# TOP_SENSOR_V2.net
KiCad netlist of a schematic drawn in EAGLE
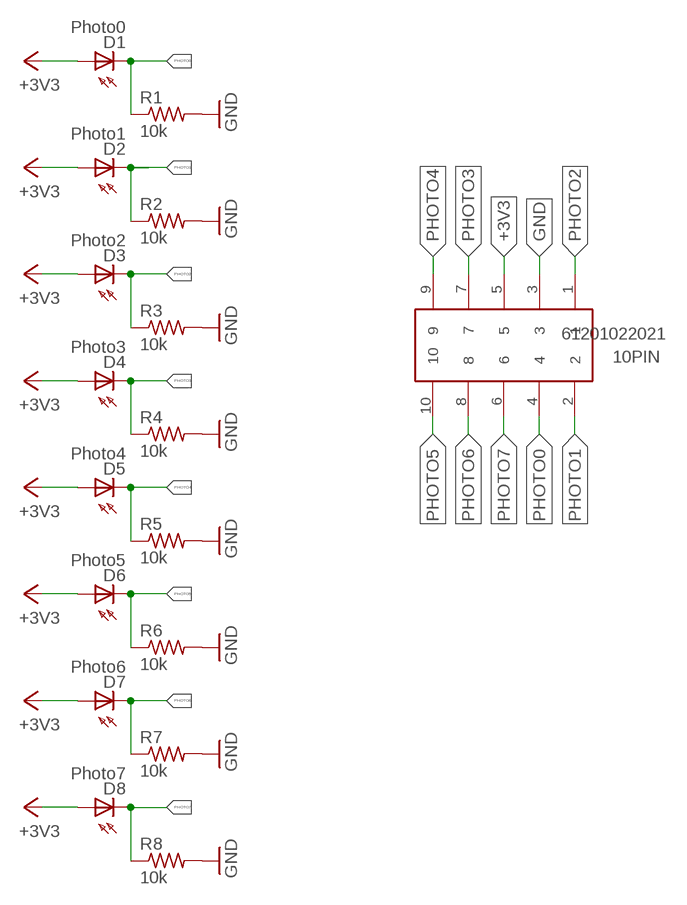
[diagram p0: schematic, sheet 1]

(export (version "E")
  (design (tool "Eeschema 10.0.6"))
  (components
    (comp (ref "10PIN")
      (value "61201022021")
      (footprint "eagle-import:61201022021")
      (libsource (lib "eagle-import") (part "61201022021"))
    )
    (comp (ref "D1")
      (value "Photo0")
      (footprint "eagle-import:BPX65")
      (fields (field (name "MPN") "BPX65."))
      (libsource (lib "eagle-import") (part "BPX65"))
    )
    (comp (ref "D2")
      (value "Photo1")
      (footprint "eagle-import:BPX65")
      (fields (field (name "MPN") "BPX65."))
      (libsource (lib "eagle-import") (part "BPX65"))
    )
    (comp (ref "D3")
      (value "Photo2")
      (footprint "eagle-import:BPX65")
      (fields (field (name "MPN") "BPX65."))
      (libsource (lib "eagle-import") (part "BPX65"))
    )
    (comp (ref "D4")
      (value "Photo3")
      (footprint "eagle-import:BPX65")
      (fields (field (name "MPN") "BPX65."))
      (libsource (lib "eagle-import") (part "BPX65"))
    )
    (comp (ref "D5")
      (value "Photo4")
      (footprint "eagle-import:BPX65")
      (fields (field (name "MPN") "BPX65."))
      (libsource (lib "eagle-import") (part "BPX65"))
    )
    (comp (ref "D6")
      (value "Photo5")
      (footprint "eagle-import:BPX65")
      (fields (field (name "MPN") "BPX65."))
      (libsource (lib "eagle-import") (part "BPX65"))
    )
    (comp (ref "D7")
      (value "Photo6")
      (footprint "eagle-import:BPX65")
      (fields (field (name "MPN") "BPX65."))
      (libsource (lib "eagle-import") (part "BPX65"))
    )
    (comp (ref "D8")
      (value "Photo7")
      (footprint "eagle-import:BPX65")
      (fields (field (name "MPN") "BPX65."))
      (libsource (lib "eagle-import") (part "BPX65"))
    )
    (comp (ref "R1")
      (value "10k")
      (footprint "eagle-import:0207_10")
      (libsource (lib "eagle-import") (part "R-US_0207/10"))
    )
    (comp (ref "R2")
      (value "10k")
      (footprint "eagle-import:0207_10")
      (libsource (lib "eagle-import") (part "R-US_0207/10"))
    )
    (comp (ref "R3")
      (value "10k")
      (footprint "eagle-import:0207_10")
      (libsource (lib "eagle-import") (part "R-US_0207/10"))
    )
    (comp (ref "R4")
      (value "10k")
      (footprint "eagle-import:0207_10")
      (libsource (lib "eagle-import") (part "R-US_0207/10"))
    )
    (comp (ref "R5")
      (value "10k")
      (footprint "eagle-import:0207_10")
      (libsource (lib "eagle-import") (part "R-US_0207/10"))
    )
    (comp (ref "R6")
      (value "10k")
      (footprint "eagle-import:0207_10")
      (libsource (lib "eagle-import") (part "R-US_0207/10"))
    )
    (comp (ref "R7")
      (value "10k")
      (footprint "eagle-import:0207_10")
      (libsource (lib "eagle-import") (part "R-US_0207/10"))
    )
    (comp (ref "R8")
      (value "10k")
      (footprint "eagle-import:0207_10")
      (libsource (lib "eagle-import") (part "R-US_0207/10"))
    )
  )
  (nets
    (net (code "1") (name "+3V3") (class "Default")
      (node (ref "10PIN") (pin "5") (pinfunction "5_5") (pintype "passive"))
      (node (ref "D1") (pin "A") (pinfunction "A_A") (pintype "passive"))
      (node (ref "D2") (pin "A") (pinfunction "A_A") (pintype "passive"))
      (node (ref "D3") (pin "A") (pinfunction "A_A") (pintype "passive"))
      (node (ref "D4") (pin "A") (pinfunction "A_A") (pintype "passive"))
      (node (ref "D5") (pin "A") (pinfunction "A_A") (pintype "passive"))
      (node (ref "D6") (pin "A") (pinfunction "A_A") (pintype "passive"))
      (node (ref "D7") (pin "A") (pinfunction "A_A") (pintype "passive"))
      (node (ref "D8") (pin "A") (pinfunction "A_A") (pintype "passive"))
    )
    (net (code "2") (name "GND") (class "Default")
      (node (ref "10PIN") (pin "3") (pinfunction "3_3") (pintype "passive"))
      (node (ref "R1") (pin "2") (pinfunction "2_2") (pintype "passive"))
      (node (ref "R2") (pin "2") (pinfunction "2_2") (pintype "passive"))
      (node (ref "R3") (pin "2") (pinfunction "2_2") (pintype "passive"))
      (node (ref "R4") (pin "2") (pinfunction "2_2") (pintype "passive"))
      (node (ref "R5") (pin "2") (pinfunction "2_2") (pintype "passive"))
      (node (ref "R6") (pin "2") (pinfunction "2_2") (pintype "passive"))
      (node (ref "R7") (pin "2") (pinfunction "2_2") (pintype "passive"))
      (node (ref "R8") (pin "2") (pinfunction "2_2") (pintype "passive"))
    )
    (net (code "3") (name "PHOTO0") (class "Default")
      (node (ref "10PIN") (pin "4") (pinfunction "4_4") (pintype "passive"))
      (node (ref "D1") (pin "K") (pinfunction "C_K") (pintype "passive"))
      (node (ref "R1") (pin "1") (pinfunction "1_1") (pintype "passive"))
    )
    (net (code "4") (name "PHOTO1") (class "Default")
      (node (ref "10PIN") (pin "2") (pinfunction "2_2") (pintype "passive"))
      (node (ref "D2") (pin "K") (pinfunction "C_K") (pintype "passive"))
      (node (ref "R2") (pin "1") (pinfunction "1_1") (pintype "passive"))
    )
    (net (code "5") (name "PHOTO2") (class "Default")
      (node (ref "10PIN") (pin "1") (pinfunction "1_1") (pintype "passive"))
      (node (ref "D3") (pin "K") (pinfunction "C_K") (pintype "passive"))
      (node (ref "R3") (pin "1") (pinfunction "1_1") (pintype "passive"))
    )
    (net (code "6") (name "PHOTO3") (class "Default")
      (node (ref "10PIN") (pin "7") (pinfunction "7_7") (pintype "passive"))
      (node (ref "D4") (pin "K") (pinfunction "C_K") (pintype "passive"))
      (node (ref "R4") (pin "1") (pinfunction "1_1") (pintype "passive"))
    )
    (net (code "7") (name "PHOTO4") (class "Default")
      (node (ref "10PIN") (pin "9") (pinfunction "9_9") (pintype "passive"))
      (node (ref "D5") (pin "K") (pinfunction "C_K") (pintype "passive"))
      (node (ref "R5") (pin "1") (pinfunction "1_1") (pintype "passive"))
    )
    (net (code "8") (name "PHOTO5") (class "Default")
      (node (ref "10PIN") (pin "10") (pinfunction "10_10") (pintype "passive"))
      (node (ref "D6") (pin "K") (pinfunction "C_K") (pintype "passive"))
      (node (ref "R6") (pin "1") (pinfunction "1_1") (pintype "passive"))
    )
    (net (code "9") (name "PHOTO6") (class "Default")
      (node (ref "10PIN") (pin "8") (pinfunction "8_8") (pintype "passive"))
      (node (ref "D7") (pin "K") (pinfunction "C_K") (pintype "passive"))
      (node (ref "R7") (pin "1") (pinfunction "1_1") (pintype "passive"))
    )
    (net (code "10") (name "PHOTO7") (class "Default")
      (node (ref "10PIN") (pin "6") (pinfunction "6_6") (pintype "passive"))
      (node (ref "D8") (pin "K") (pinfunction "C_K") (pintype "passive"))
      (node (ref "R8") (pin "1") (pinfunction "1_1") (pintype "passive"))
    )
  )
)
